# BMI160.net
KiCad netlist of a schematic drawn in Altium Designer
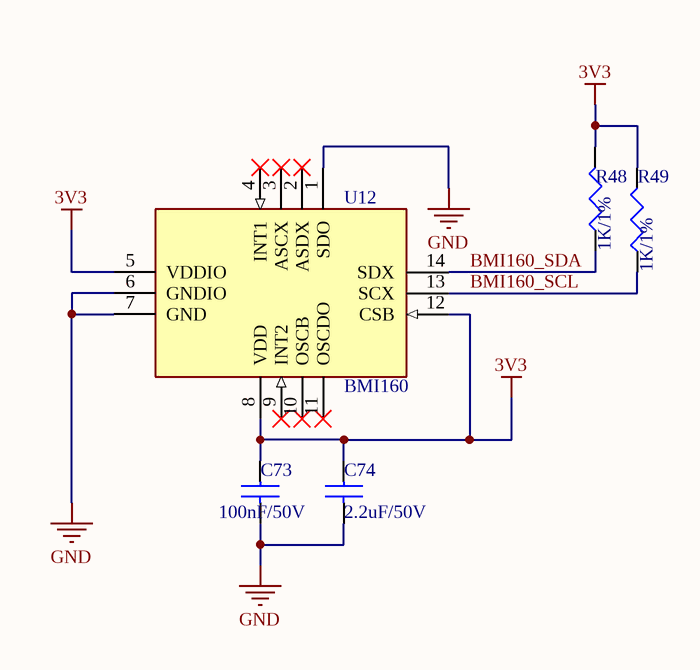
[diagram p0: BMI160.SchDoc]

(export (version "E")
  (design (tool "Eeschema 10.0.6"))
  (components
    (comp (ref "C73") (value "100nF/50V") (footprint "C0402") (libsource (lib "*") (part "CAP NP")))
    (comp (ref "C74") (value "2.2uF/50V") (footprint "C0402") (libsource (lib "*") (part "CAP NP")))
    (comp (ref "R48") (value "1K/1%") (footprint "R0402") (libsource (lib "*") (part "RESISTOR")))
    (comp (ref "R49") (value "1K/1%") (footprint "R0402") (libsource (lib "*") (part "RESISTOR")))
    (comp (ref "U12")
      (value "BMI160")
      (footprint "PQFN50P300X250X88-14N")
      (description "Integrated Circuit")
      (fields (field (name "MOUSER PART NUMBER") "262-BMI160"))
      (libsource (lib "VESC_DEVICE_Library") (part "BMI160"))
    )
  )
  (nets
    (net (code "1") (name "/BMI160_SCL") (class "Default")
      (node (ref "R49") (pin "1") (pinfunction "1_1") (pintype "passive"))
      (node (ref "U12") (pin "13") (pinfunction "SCX_13") (pintype "passive"))
    )
    (net (code "2") (name "/BMI160_SDA") (class "Default")
      (node (ref "R48") (pin "1") (pinfunction "1_1") (pintype "passive"))
      (node (ref "U12") (pin "14") (pinfunction "SDX_14") (pintype "passive"))
    )
    (net (code "3") (name "3V3") (class "Default")
      (node (ref "C73") (pin "1") (pinfunction "1_1") (pintype "passive"))
      (node (ref "C74") (pin "1") (pinfunction "1_1") (pintype "passive"))
      (node (ref "R48") (pin "2") (pinfunction "2_2") (pintype "passive"))
      (node (ref "R49") (pin "2") (pinfunction "2_2") (pintype "passive"))
      (node (ref "U12") (pin "12") (pinfunction "CSB_12") (pintype "input"))
      (node (ref "U12") (pin "5") (pinfunction "VDDIO_5") (pintype "power_in"))
      (node (ref "U12") (pin "8") (pinfunction "VDD_8") (pintype "power_in"))
    )
    (net (code "4") (name "GND") (class "Default")
      (node (ref "C73") (pin "2") (pinfunction "2_2") (pintype "passive"))
      (node (ref "C74") (pin "2") (pinfunction "2_2") (pintype "passive"))
      (node (ref "U12") (pin "1") (pinfunction "SDO_1") (pintype "passive"))
      (node (ref "U12") (pin "6") (pinfunction "GNDIO_6") (pintype "power_in"))
      (node (ref "U12") (pin "7") (pinfunction "GND_7") (pintype "power_in"))
    )
    (net (code "5") (name "unconnected-(U12-ASCX-Pad3)") (class "Default")
      (node (ref "U12") (pin "3") (pinfunction "ASCX_3") (pintype "passive+no_connect"))
    )
    (net (code "6") (name "unconnected-(U12-ASDX-Pad2)") (class "Default")
      (node (ref "U12") (pin "2") (pinfunction "ASDX_2") (pintype "passive+no_connect"))
    )
    (net (code "7") (name "unconnected-(U12-INT1-Pad4)") (class "Default")
      (node (ref "U12") (pin "4") (pinfunction "INT1_4") (pintype "input+no_connect"))
    )
    (net (code "8") (name "unconnected-(U12-INT2-Pad9)") (class "Default")
      (node (ref "U12") (pin "9") (pinfunction "INT2_9") (pintype "input+no_connect"))
    )
    (net (code "9") (name "unconnected-(U12-OSCB-Pad10)") (class "Default")
      (node (ref "U12") (pin "10") (pinfunction "OSCB_10") (pintype "passive+no_connect"))
    )
    (net (code "10") (name "unconnected-(U12-OSCDO-Pad11)") (class "Default")
      (node (ref "U12") (pin "11") (pinfunction "OSCDO_11") (pintype "passive+no_connect"))
    )
  )
)
